# Controller.net
KiCad netlist of a schematic drawn in Altium Designer
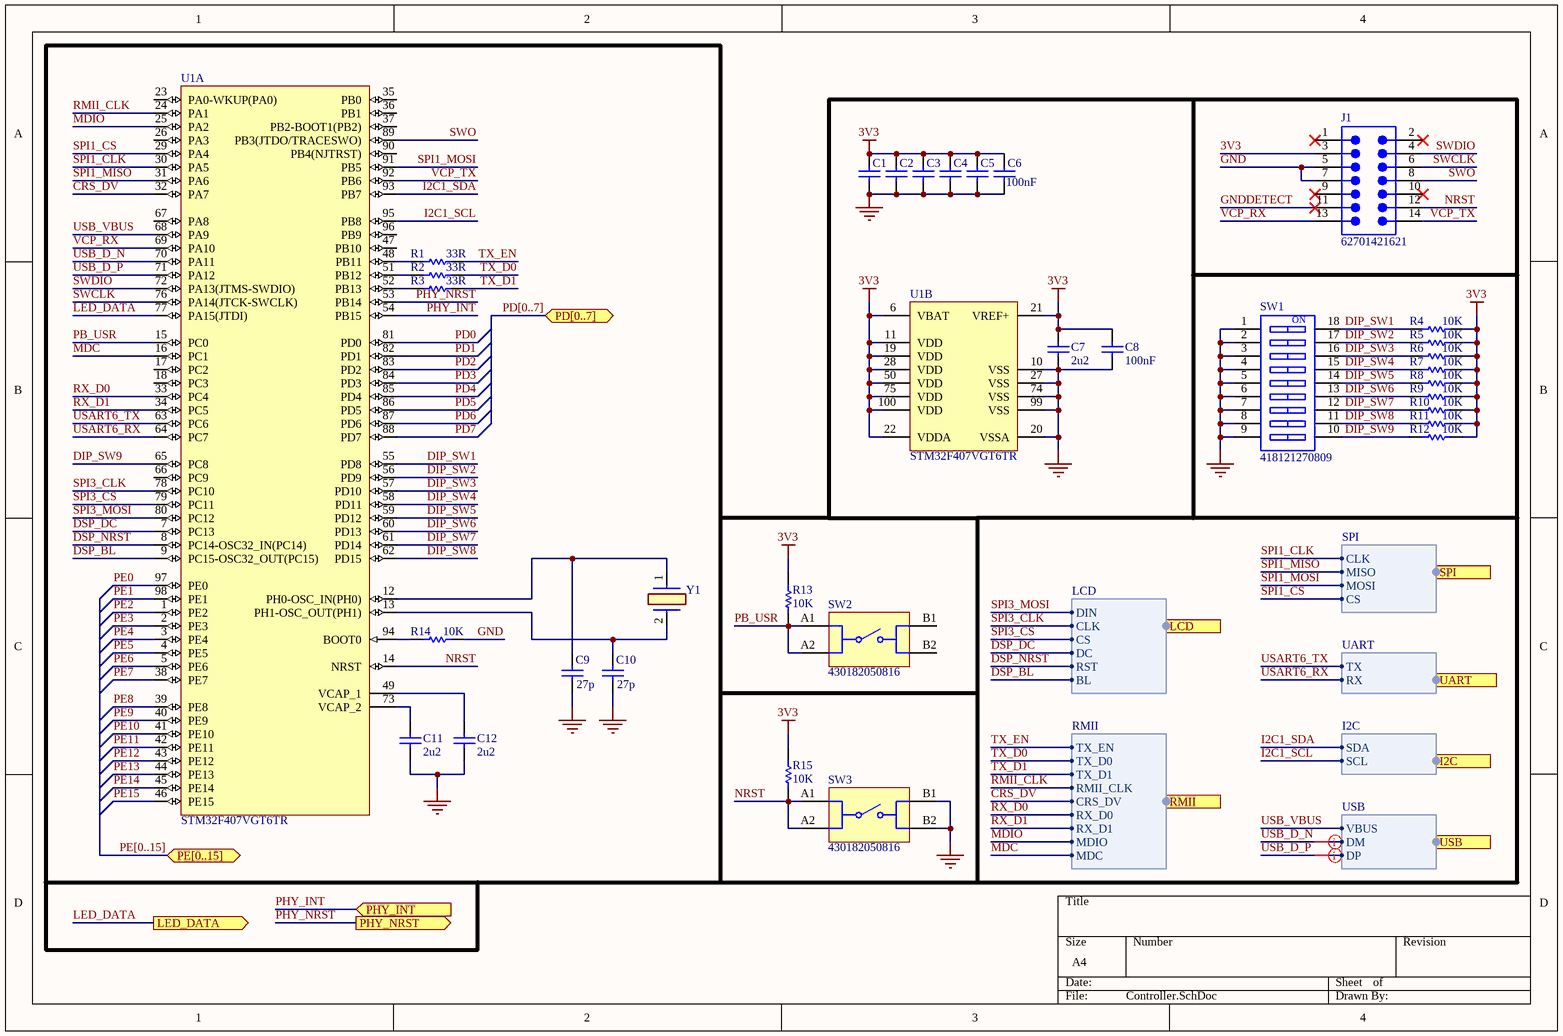
[diagram p0: Controller.SchDoc]

(export (version "E")
  (design (tool "Eeschema 10.0.6"))
  (components
    (comp (ref "C1")
      (value "100nF")
      (footprint "0603")
      (description "Capacitor 100V \r\n0603")
      (libsource (lib "Schlib1") (part "C0603C104K1RACAUTO"))
    )
    (comp (ref "C2")
      (value "100nF")
      (footprint "0603")
      (description "Capacitor 100V \r\n0603")
      (libsource (lib "Schlib1") (part "C0603C104K1RACAUTO"))
    )
    (comp (ref "C3")
      (value "100nF")
      (footprint "0603")
      (description "Capacitor 100V \r\n0603")
      (libsource (lib "Schlib1") (part "C0603C104K1RACAUTO"))
    )
    (comp (ref "C4")
      (value "100nF")
      (footprint "0603")
      (description "Capacitor 100V \r\n0603")
      (libsource (lib "Schlib1") (part "C0603C104K1RACAUTO"))
    )
    (comp (ref "C5")
      (value "100nF")
      (footprint "0603")
      (description "Capacitor 100V \r\n0603")
      (libsource (lib "Schlib1") (part "C0603C104K1RACAUTO"))
    )
    (comp (ref "C6")
      (value "100nF")
      (footprint "0603")
      (description "Capacitor 100V \r\n0603")
      (libsource (lib "Schlib1") (part "C0603C104K1RACAUTO"))
    )
    (comp (ref "C7")
      (value "2u2")
      (footprint "1206")
      (description "Capacitor 50V\r\n1206")
      (libsource (lib "Schlib1") (part "C1206C225K5RACAUTO7210"))
    )
    (comp (ref "C8")
      (value "100nF")
      (footprint "0603")
      (description "Capacitor 100V \r\n0603")
      (libsource (lib "Schlib1") (part "C0603C104K1RACAUTO"))
    )
    (comp (ref "C9")
      (value "27p")
      (footprint "0603")
      (description "Capacitor 100V \r\n0603")
      (libsource (lib "Schlib1") (part "C0603C270K1HACTU"))
    )
    (comp (ref "C10")
      (value "27p")
      (footprint "0603")
      (description "Capacitor 100V \r\n0603")
      (libsource (lib "Schlib1") (part "C0603C270K1HACTU"))
    )
    (comp (ref "C11")
      (value "2u2")
      (footprint "1206")
      (description "Capacitor 50V\r\n1206")
      (libsource (lib "Schlib1") (part "C1206C225K5RACAUTO7210"))
    )
    (comp (ref "C12")
      (value "2u2")
      (footprint "1206")
      (description "Capacitor 50V\r\n1206")
      (libsource (lib "Schlib1") (part "C1206C225K5RACAUTO7210"))
    )
    (comp (ref "J1")
      (value "62701421621")
      (footprint "62701421621")
      (description "62701421621 Conn, Header, 14Pos, 2Row, 1.27Mm Rohs Compliant: Yes")
      (libsource (lib "Altium Content Vault") (part "Header_Male_2R_14P"))
    )
    (comp (ref "R1")
      (value "33R")
      (footprint "0603")
      (description "Resistor 0.1W")
      (libsource (lib "Schlib1") (part "CRCW060333R0FKEA"))
    )
    (comp (ref "R2")
      (value "33R")
      (footprint "0603")
      (description "Resistor 0.1W")
      (libsource (lib "Schlib1") (part "CRCW060333R0FKEA"))
    )
    (comp (ref "R3")
      (value "33R")
      (footprint "0603")
      (description "Resistor 0.1W")
      (libsource (lib "Schlib1") (part "CRCW060333R0FKEA"))
    )
    (comp (ref "R4")
      (value "10K")
      (footprint "0603")
      (description "Resistor 0.1W")
      (libsource (lib "Schlib1") (part "CRCW060310K0FKEA"))
    )
    (comp (ref "R5")
      (value "10K")
      (footprint "0603")
      (description "Resistor 0.1W")
      (libsource (lib "Schlib1") (part "CRCW060310K0FKEA"))
    )
    (comp (ref "R6")
      (value "10K")
      (footprint "0603")
      (description "Resistor 0.1W")
      (libsource (lib "Schlib1") (part "CRCW060310K0FKEA"))
    )
    (comp (ref "R7")
      (value "10K")
      (footprint "0603")
      (description "Resistor 0.1W")
      (libsource (lib "Schlib1") (part "CRCW060310K0FKEA"))
    )
    (comp (ref "R8")
      (value "10K")
      (footprint "0603")
      (description "Resistor 0.1W")
      (libsource (lib "Schlib1") (part "CRCW060310K0FKEA"))
    )
    (comp (ref "R9")
      (value "10K")
      (footprint "0603")
      (description "Resistor 0.1W")
      (libsource (lib "Schlib1") (part "CRCW060310K0FKEA"))
    )
    (comp (ref "R10")
      (value "10K")
      (footprint "0603")
      (description "Resistor 0.1W")
      (libsource (lib "Schlib1") (part "CRCW060310K0FKEA"))
    )
    (comp (ref "R11")
      (value "10K")
      (footprint "0603")
      (description "Resistor 0.1W")
      (libsource (lib "Schlib1") (part "CRCW060310K0FKEA"))
    )
    (comp (ref "R12")
      (value "10K")
      (footprint "0603")
      (description "Resistor 0.1W")
      (libsource (lib "Schlib1") (part "CRCW060310K0FKEA"))
    )
    (comp (ref "R13")
      (value "10K")
      (footprint "0603")
      (description "Resistor 0.1W")
      (libsource (lib "Schlib1") (part "CRCW060310K0FKEA"))
    )
    (comp (ref "R14")
      (value "10K")
      (footprint "0603")
      (description "Resistor 0.1W")
      (libsource (lib "Schlib1") (part "CRCW060310K0FKEA"))
    )
    (comp (ref "R15")
      (value "10K")
      (footprint "0603")
      (description "Resistor 0.1W")
      (libsource (lib "Schlib1") (part "CRCW060310K0FKEA"))
    )
    (comp (ref "SW1")
      (value "418121270809")
      (footprint "418121270809")
      (libsource (lib "Altium Content Vault") (part "DIP-9"))
    )
    (comp (ref "SW2")
      (value "430182050816")
      (footprint "430182050816")
      (description "Switch Tactile N.O. SPST Round Button Gull Wing 0.05A 12VDC 1000000Cycles 1.57N SMD Reel")
      (libsource (lib "Altium Content Vault") (part "SPST-NO_4P"))
    )
    (comp (ref "SW3")
      (value "430182050816")
      (footprint "430182050816")
      (description "Switch Tactile N.O. SPST Round Button Gull Wing 0.05A 12VDC 1000000Cycles 1.57N SMD Reel")
      (libsource (lib "Altium Content Vault") (part "SPST-NO_4P"))
    )
    (comp (ref "U1")
      (value "STM32F407VGT6TR")
      (footprint "STM-LQFP100_V")
      (fields (field (name "MANUFACTURER") "STMicroelectronics"))
      (libsource (lib "Altium Content Vault") (part "MC-ARM-STM32F40X_41X-SQ100"))
    )
    (comp (ref "Y1")
      (value "ABLS7M-16.000MHZ-B-2-T")
      (footprint "ABLS7")
      (description "Crystal or Oscillator")
      (fields (field (name "MOUSER PART NUMBER") "815-ABLS7M-16-B-2-T"))
      (libsource (lib "Schlib1") (part "ABLS7M-16.000MHZ-B-2-T"))
    )
  )
  (nets
    (net (code "7") (name "/CRS_DV") (class "Default")
      (node (ref "U1") (pin "32") (pinfunction "PA7_32") (pintype "bidirectional"))
    )
    (net (code "8") (name "/DIP_SW1") (class "Default")
      (node (ref "R4") (pin "1") (pinfunction "1_1") (pintype "passive"))
      (node (ref "SW1") (pin "18") (pinfunction "18_18") (pintype "passive"))
      (node (ref "U1") (pin "55") (pinfunction "PD8_55") (pintype "bidirectional"))
    )
    (net (code "9") (name "/DIP_SW2") (class "Default")
      (node (ref "R5") (pin "1") (pinfunction "1_1") (pintype "passive"))
      (node (ref "SW1") (pin "17") (pinfunction "17_17") (pintype "passive"))
      (node (ref "U1") (pin "56") (pinfunction "PD9_56") (pintype "bidirectional"))
    )
    (net (code "10") (name "/DIP_SW3") (class "Default")
      (node (ref "R6") (pin "1") (pinfunction "1_1") (pintype "passive"))
      (node (ref "SW1") (pin "16") (pinfunction "16_16") (pintype "passive"))
      (node (ref "U1") (pin "57") (pinfunction "PD10_57") (pintype "bidirectional"))
    )
    (net (code "11") (name "/DIP_SW4") (class "Default")
      (node (ref "R7") (pin "1") (pinfunction "1_1") (pintype "passive"))
      (node (ref "SW1") (pin "15") (pinfunction "15_15") (pintype "passive"))
      (node (ref "U1") (pin "58") (pinfunction "PD11_58") (pintype "bidirectional"))
    )
    (net (code "12") (name "/DIP_SW5") (class "Default")
      (node (ref "R8") (pin "1") (pinfunction "1_1") (pintype "passive"))
      (node (ref "SW1") (pin "14") (pinfunction "14_14") (pintype "passive"))
      (node (ref "U1") (pin "59") (pinfunction "PD12_59") (pintype "bidirectional"))
    )
    (net (code "13") (name "/DIP_SW6") (class "Default")
      (node (ref "R9") (pin "1") (pinfunction "1_1") (pintype "passive"))
      (node (ref "SW1") (pin "13") (pinfunction "13_13") (pintype "passive"))
      (node (ref "U1") (pin "60") (pinfunction "PD13_60") (pintype "bidirectional"))
    )
    (net (code "14") (name "/DIP_SW7") (class "Default")
      (node (ref "R10") (pin "1") (pinfunction "1_1") (pintype "passive"))
      (node (ref "SW1") (pin "12") (pinfunction "12_12") (pintype "passive"))
      (node (ref "U1") (pin "61") (pinfunction "PD14_61") (pintype "bidirectional"))
    )
    (net (code "15") (name "/DIP_SW8") (class "Default")
      (node (ref "R11") (pin "1") (pinfunction "1_1") (pintype "passive"))
      (node (ref "SW1") (pin "11") (pinfunction "11_11") (pintype "passive"))
      (node (ref "U1") (pin "62") (pinfunction "PD15_62") (pintype "bidirectional"))
    )
    (net (code "16") (name "/DIP_SW9") (class "Default")
      (node (ref "R12") (pin "1") (pinfunction "1_1") (pintype "passive"))
      (node (ref "SW1") (pin "10") (pinfunction "10_10") (pintype "passive"))
      (node (ref "U1") (pin "65") (pinfunction "PC8_65") (pintype "bidirectional"))
    )
    (net (code "17") (name "/DSP_BL") (class "Default")
      (node (ref "U1") (pin "9") (pinfunction "PC15-OSC32_OUT(PC15)_9") (pintype "bidirectional"))
    )
    (net (code "18") (name "/DSP_DC") (class "Default")
      (node (ref "U1") (pin "7") (pinfunction "PC13_7") (pintype "bidirectional"))
    )
    (net (code "19") (name "/DSP_NRST") (class "Default")
      (node (ref "U1") (pin "8") (pinfunction "PC14-OSC32_IN(PC14)_8") (pintype "bidirectional"))
    )
    (net (code "20") (name "/GNDDETECT") (class "Default")
      (node (ref "J1") (pin "11") (pinfunction "11_11") (pintype "passive+no_connect"))
    )
    (net (code "21") (name "/I2C1_SCL") (class "Default")
      (node (ref "U1") (pin "95") (pinfunction "PB8_95") (pintype "bidirectional"))
    )
    (net (code "22") (name "/I2C1_SDA") (class "Default")
      (node (ref "U1") (pin "93") (pinfunction "PB7_93") (pintype "bidirectional"))
    )
    (net (code "23") (name "/LED_DATA") (class "Default")
      (node (ref "U1") (pin "77") (pinfunction "PA15(JTDI)_77") (pintype "bidirectional"))
    )
    (net (code "24") (name "/MDC") (class "Default")
      (node (ref "U1") (pin "16") (pinfunction "PC1_16") (pintype "bidirectional"))
    )
    (net (code "25") (name "/MDIO") (class "Default")
      (node (ref "U1") (pin "25") (pinfunction "PA2_25") (pintype "bidirectional"))
    )
    (net (code "26") (name "/NRST") (class "Default")
      (node (ref "J1") (pin "12") (pinfunction "12_12") (pintype "passive"))
      (node (ref "R15") (pin "1") (pinfunction "1_1") (pintype "passive"))
      (node (ref "SW3") (pin "A1") (pinfunction "A1_A1") (pintype "passive"))
      (node (ref "SW3") (pin "A2") (pinfunction "A2_A2") (pintype "passive"))
      (node (ref "U1") (pin "14") (pinfunction "NRST_14") (pintype "bidirectional"))
    )
    (net (code "27") (name "/PB_USR") (class "Default")
      (node (ref "R13") (pin "1") (pinfunction "1_1") (pintype "passive"))
      (node (ref "SW2") (pin "A1") (pinfunction "A1_A1") (pintype "passive"))
      (node (ref "SW2") (pin "A2") (pinfunction "A2_A2") (pintype "passive"))
      (node (ref "U1") (pin "15") (pinfunction "PC0_15") (pintype "bidirectional"))
    )
    (net (code "28") (name "/PD0") (class "Default")
      (node (ref "U1") (pin "81") (pinfunction "PD0_81") (pintype "bidirectional"))
    )
    (net (code "29") (name "/PD1") (class "Default")
      (node (ref "U1") (pin "82") (pinfunction "PD1_82") (pintype "bidirectional"))
    )
    (net (code "30") (name "/PD2") (class "Default")
      (node (ref "U1") (pin "83") (pinfunction "PD2_83") (pintype "bidirectional"))
    )
    (net (code "31") (name "/PD3") (class "Default")
      (node (ref "U1") (pin "84") (pinfunction "PD3_84") (pintype "bidirectional"))
    )
    (net (code "32") (name "/PD4") (class "Default")
      (node (ref "U1") (pin "85") (pinfunction "PD4_85") (pintype "bidirectional"))
    )
    (net (code "33") (name "/PD5") (class "Default")
      (node (ref "U1") (pin "86") (pinfunction "PD5_86") (pintype "bidirectional"))
    )
    (net (code "34") (name "/PD6") (class "Default")
      (node (ref "U1") (pin "87") (pinfunction "PD6_87") (pintype "bidirectional"))
    )
    (net (code "35") (name "/PD7") (class "Default")
      (node (ref "U1") (pin "88") (pinfunction "PD7_88") (pintype "bidirectional"))
    )
    (net (code "37") (name "/PE0") (class "Default")
      (node (ref "U1") (pin "97") (pinfunction "PE0_97") (pintype "bidirectional"))
    )
    (net (code "38") (name "/PE1") (class "Default")
      (node (ref "U1") (pin "98") (pinfunction "PE1_98") (pintype "bidirectional"))
    )
    (net (code "39") (name "/PE2") (class "Default")
      (node (ref "U1") (pin "1") (pinfunction "PE2_1") (pintype "bidirectional"))
    )
    (net (code "40") (name "/PE3") (class "Default")
      (node (ref "U1") (pin "2") (pinfunction "PE3_2") (pintype "bidirectional"))
    )
    (net (code "41") (name "/PE4") (class "Default")
      (node (ref "U1") (pin "3") (pinfunction "PE4_3") (pintype "bidirectional"))
    )
    (net (code "42") (name "/PE5") (class "Default")
      (node (ref "U1") (pin "4") (pinfunction "PE5_4") (pintype "bidirectional"))
    )
    (net (code "43") (name "/PE6") (class "Default")
      (node (ref "U1") (pin "5") (pinfunction "PE6_5") (pintype "bidirectional"))
    )
    (net (code "44") (name "/PE7") (class "Default")
      (node (ref "U1") (pin "38") (pinfunction "PE7_38") (pintype "bidirectional"))
    )
    (net (code "45") (name "/PE8") (class "Default")
      (node (ref "U1") (pin "39") (pinfunction "PE8_39") (pintype "bidirectional"))
    )
    (net (code "46") (name "/PE9") (class "Default")
      (node (ref "U1") (pin "40") (pinfunction "PE9_40") (pintype "bidirectional"))
    )
    (net (code "47") (name "/PE10") (class "Default")
      (node (ref "U1") (pin "41") (pinfunction "PE10_41") (pintype "bidirectional"))
    )
    (net (code "48") (name "/PE11") (class "Default")
      (node (ref "U1") (pin "42") (pinfunction "PE11_42") (pintype "bidirectional"))
    )
    (net (code "49") (name "/PE12") (class "Default")
      (node (ref "U1") (pin "43") (pinfunction "PE12_43") (pintype "bidirectional"))
    )
    (net (code "50") (name "/PE13") (class "Default")
      (node (ref "U1") (pin "44") (pinfunction "PE13_44") (pintype "bidirectional"))
    )
    (net (code "51") (name "/PE14") (class "Default")
      (node (ref "U1") (pin "45") (pinfunction "PE14_45") (pintype "bidirectional"))
    )
    (net (code "52") (name "/PE15") (class "Default")
      (node (ref "U1") (pin "46") (pinfunction "PE15_46") (pintype "bidirectional"))
    )
    (net (code "54") (name "/PHY_INT") (class "Default")
      (node (ref "U1") (pin "54") (pinfunction "PB15_54") (pintype "bidirectional"))
    )
    (net (code "55") (name "/PHY_NRST") (class "Default")
      (node (ref "U1") (pin "53") (pinfunction "PB14_53") (pintype "bidirectional"))
    )
    (net (code "56") (name "/RMII_CLK") (class "Default")
      (node (ref "U1") (pin "24") (pinfunction "PA1_24") (pintype "bidirectional"))
    )
    (net (code "57") (name "/RX_D0") (class "Default")
      (node (ref "U1") (pin "33") (pinfunction "PC4_33") (pintype "bidirectional"))
    )
    (net (code "58") (name "/RX_D1") (class "Default")
      (node (ref "U1") (pin "34") (pinfunction "PC5_34") (pintype "bidirectional"))
    )
    (net (code "59") (name "/SPI1_CLK") (class "Default")
      (node (ref "U1") (pin "30") (pinfunction "PA5_30") (pintype "bidirectional"))
    )
    (net (code "60") (name "/SPI1_CS") (class "Default")
      (node (ref "U1") (pin "29") (pinfunction "PA4_29") (pintype "bidirectional"))
    )
    (net (code "61") (name "/SPI1_MISO") (class "Default")
      (node (ref "U1") (pin "31") (pinfunction "PA6_31") (pintype "bidirectional"))
    )
    (net (code "62") (name "/SPI1_MOSI") (class "Default")
      (node (ref "U1") (pin "91") (pinfunction "PB5_91") (pintype "bidirectional"))
    )
    (net (code "63") (name "/SPI3_CLK") (class "Default")
      (node (ref "U1") (pin "78") (pinfunction "PC10_78") (pintype "bidirectional"))
    )
    (net (code "64") (name "/SPI3_CS") (class "Default")
      (node (ref "U1") (pin "79") (pinfunction "PC11_79") (pintype "bidirectional"))
    )
    (net (code "65") (name "/SPI3_MOSI") (class "Default")
      (node (ref "U1") (pin "80") (pinfunction "PC12_80") (pintype "bidirectional"))
    )
    (net (code "66") (name "/SWCLK") (class "Default")
      (node (ref "J1") (pin "6") (pinfunction "6_6") (pintype "passive"))
      (node (ref "U1") (pin "76") (pinfunction "PA14(JTCK-SWCLK)_76") (pintype "bidirectional"))
    )
    (net (code "67") (name "/SWDIO") (class "Default")
      (node (ref "J1") (pin "4") (pinfunction "4_4") (pintype "passive"))
      (node (ref "U1") (pin "72") (pinfunction "PA13(JTMS-SWDIO)_72") (pintype "bidirectional"))
    )
    (net (code "68") (name "/SWO") (class "Default")
      (node (ref "J1") (pin "8") (pinfunction "8_8") (pintype "passive"))
      (node (ref "U1") (pin "89") (pinfunction "PB3(JTDO/TRACESWO)_89") (pintype "bidirectional"))
    )
    (net (code "69") (name "/TX_D0") (class "Default")
      (node (ref "R2") (pin "2") (pinfunction "2_2") (pintype "passive"))
    )
    (net (code "70") (name "/TX_D1") (class "Default")
      (node (ref "R3") (pin "2") (pinfunction "2_2") (pintype "passive"))
    )
    (net (code "71") (name "/TX_EN") (class "Default")
      (node (ref "R1") (pin "2") (pinfunction "2_2") (pintype "passive"))
    )
    (net (code "72") (name "/USART6_RX") (class "Default")
      (node (ref "U1") (pin "64") (pinfunction "PC7_64") (pintype "bidirectional"))
    )
    (net (code "73") (name "/USART6_TX") (class "Default")
      (node (ref "U1") (pin "63") (pinfunction "PC6_63") (pintype "bidirectional"))
    )
    (net (code "74") (name "/USB_D_N") (class "Default")
      (node (ref "U1") (pin "70") (pinfunction "PA11_70") (pintype "bidirectional"))
    )
    (net (code "75") (name "/USB_D_P") (class "Default")
      (node (ref "U1") (pin "71") (pinfunction "PA12_71") (pintype "bidirectional"))
    )
    (net (code "76") (name "/USB_VBUS") (class "Default")
      (node (ref "U1") (pin "68") (pinfunction "PA9_68") (pintype "bidirectional"))
    )
    (net (code "77") (name "/VCP_RX") (class "Default")
      (node (ref "J1") (pin "13") (pinfunction "13_13") (pintype "passive"))
      (node (ref "U1") (pin "69") (pinfunction "PA10_69") (pintype "bidirectional"))
    )
    (net (code "78") (name "/VCP_TX") (class "Default")
      (node (ref "J1") (pin "14") (pinfunction "14_14") (pintype "passive"))
      (node (ref "U1") (pin "92") (pinfunction "PB6_92") (pintype "bidirectional"))
    )
    (net (code "85") (name "3V3") (class "Default")
      (node (ref "C1") (pin "2") (pinfunction "2_2") (pintype "passive"))
      (node (ref "C2") (pin "2") (pinfunction "2_2") (pintype "passive"))
      (node (ref "C3") (pin "2") (pinfunction "2_2") (pintype "passive"))
      (node (ref "C4") (pin "2") (pinfunction "2_2") (pintype "passive"))
      (node (ref "C5") (pin "2") (pinfunction "2_2") (pintype "passive"))
      (node (ref "C6") (pin "2") (pinfunction "2_2") (pintype "passive"))
      (node (ref "C7") (pin "2") (pinfunction "2_2") (pintype "passive"))
      (node (ref "C8") (pin "2") (pinfunction "2_2") (pintype "passive"))
      (node (ref "J1") (pin "3") (pinfunction "3_3") (pintype "passive"))
      (node (ref "R10") (pin "2") (pinfunction "2_2") (pintype "passive"))
      (node (ref "R11") (pin "2") (pinfunction "2_2") (pintype "passive"))
      (node (ref "R12") (pin "2") (pinfunction "2_2") (pintype "passive"))
      (node (ref "R13") (pin "2") (pinfunction "2_2") (pintype "passive"))
      (node (ref "R15") (pin "2") (pinfunction "2_2") (pintype "passive"))
      (node (ref "R4") (pin "2") (pinfunction "2_2") (pintype "passive"))
      (node (ref "R5") (pin "2") (pinfunction "2_2") (pintype "passive"))
      (node (ref "R6") (pin "2") (pinfunction "2_2") (pintype "passive"))
      (node (ref "R7") (pin "2") (pinfunction "2_2") (pintype "passive"))
      (node (ref "R8") (pin "2") (pinfunction "2_2") (pintype "passive"))
      (node (ref "R9") (pin "2") (pinfunction "2_2") (pintype "passive"))
      (node (ref "U1") (pin "100") (pinfunction "VDD_100") (pintype "power_in"))
      (node (ref "U1") (pin "11") (pinfunction "VDD_11") (pintype "power_in"))
      (node (ref "U1") (pin "19") (pinfunction "VDD_19") (pintype "power_in"))
      (node (ref "U1") (pin "21") (pinfunction "VREF+_21") (pintype "power_in"))
      (node (ref "U1") (pin "22") (pinfunction "VDDA_22") (pintype "power_in"))
      (node (ref "U1") (pin "28") (pinfunction "VDD_28") (pintype "power_in"))
      (node (ref "U1") (pin "50") (pinfunction "VDD_50") (pintype "power_in"))
      (node (ref "U1") (pin "6") (pinfunction "VBAT_6") (pintype "power_in"))
      (node (ref "U1") (pin "75") (pinfunction "VDD_75") (pintype "power_in"))
    )
    (net (code "86") (name "GND") (class "Default")
      (node (ref "C1") (pin "1") (pinfunction "1_1") (pintype "passive"))
      (node (ref "C10") (pin "1") (pinfunction "1_1") (pintype "passive"))
      (node (ref "C11") (pin "1") (pinfunction "1_1") (pintype "passive"))
      (node (ref "C12") (pin "1") (pinfunction "1_1") (pintype "passive"))
      (node (ref "C2") (pin "1") (pinfunction "1_1") (pintype "passive"))
      (node (ref "C3") (pin "1") (pinfunction "1_1") (pintype "passive"))
      (node (ref "C4") (pin "1") (pinfunction "1_1") (pintype "passive"))
      (node (ref "C5") (pin "1") (pinfunction "1_1") (pintype "passive"))
      (node (ref "C6") (pin "1") (pinfunction "1_1") (pintype "passive"))
      (node (ref "C7") (pin "1") (pinfunction "1_1") (pintype "passive"))
      (node (ref "C8") (pin "1") (pinfunction "1_1") (pintype "passive"))
      (node (ref "C9") (pin "1") (pinfunction "1_1") (pintype "passive"))
      (node (ref "J1") (pin "5") (pinfunction "5_5") (pintype "passive"))
      (node (ref "J1") (pin "7") (pinfunction "7_7") (pintype "passive"))
      (node (ref "R14") (pin "2") (pinfunction "2_2") (pintype "passive"))
      (node (ref "SW1") (pin "1") (pinfunction "1_1") (pintype "passive"))
      (node (ref "SW1") (pin "2") (pinfunction "2_2") (pintype "passive"))
      (node (ref "SW1") (pin "3") (pinfunction "3_3") (pintype "passive"))
      (node (ref "SW1") (pin "4") (pinfunction "4_4") (pintype "passive"))
      (node (ref "SW1") (pin "5") (pinfunction "5_5") (pintype "passive"))
      (node (ref "SW1") (pin "6") (pinfunction "6_6") (pintype "passive"))
      (node (ref "SW1") (pin "7") (pinfunction "7_7") (pintype "passive"))
      (node (ref "SW1") (pin "8") (pinfunction "8_8") (pintype "passive"))
      (node (ref "SW1") (pin "9") (pinfunction "9_9") (pintype "passive"))
      (node (ref "SW3") (pin "B1") (pinfunction "B1_B1") (pintype "passive"))
      (node (ref "SW3") (pin "B2") (pinfunction "B2_B2") (pintype "passive"))
      (node (ref "U1") (pin "10") (pinfunction "VSS_10") (pintype "power_in"))
      (node (ref "U1") (pin "20") (pinfunction "VSSA_20") (pintype "power_in"))
      (node (ref "U1") (pin "27") (pinfunction "VSS_27") (pintype "power_in"))
      (node (ref "U1") (pin "74") (pinfunction "VSS_74") (pintype "power_in"))
      (node (ref "U1") (pin "99") (pinfunction "VSS_99") (pintype "power_in"))
    )
    (net (code "87") (name "Net-(U1A-BOOT0)") (class "Default")
      (node (ref "R14") (pin "1") (pinfunction "1_1") (pintype "passive"))
      (node (ref "U1") (pin "94") (pinfunction "BOOT0_94") (pintype "input"))
    )
    (net (code "88") (name "Net-(U1A-PB11)") (class "Default")
      (node (ref "R1") (pin "1") (pinfunction "1_1") (pintype "passive"))
      (node (ref "U1") (pin "48") (pinfunction "PB11_48") (pintype "bidirectional"))
    )
    (net (code "89") (name "Net-(U1A-PB12)") (class "Default")
      (node (ref "R2") (pin "1") (pinfunction "1_1") (pintype "passive"))
      (node (ref "U1") (pin "51") (pinfunction "PB12_51") (pintype "bidirectional"))
    )
    (net (code "90") (name "Net-(U1A-PB13)") (class "Default")
      (node (ref "R3") (pin "1") (pinfunction "1_1") (pintype "passive"))
      (node (ref "U1") (pin "52") (pinfunction "PB13_52") (pintype "bidirectional"))
    )
    (net (code "91") (name "Net-(U1A-PH0-OSC_IN(PH0))") (class "Default")
      (node (ref "C9") (pin "2") (pinfunction "2_2") (pintype "passive"))
      (node (ref "U1") (pin "12") (pinfunction "PH0-OSC_IN(PH0)_12") (pintype "bidirectional"))
      (node (ref "Y1") (pin "1") (pinfunction "1_1") (pintype "passive"))
    )
    (net (code "92") (name "Net-(U1A-PH1-OSC_OUT(PH1))") (class "Default")
      (node (ref "C10") (pin "2") (pinfunction "2_2") (pintype "passive"))
      (node (ref "U1") (pin "13") (pinfunction "PH1-OSC_OUT(PH1)_13") (pintype "bidirectional"))
      (node (ref "Y1") (pin "2") (pinfunction "2_2") (pintype "passive"))
    )
    (net (code "93") (name "Net-(U1A-VCAP_1)") (class "Default")
      (node (ref "C12") (pin "2") (pinfunction "2_2") (pintype "passive"))
      (node (ref "U1") (pin "49") (pinfunction "VCAP_1_49") (pintype "power_in"))
    )
    (net (code "94") (name "Net-(U1A-VCAP_2)") (class "Default")
      (node (ref "C11") (pin "2") (pinfunction "2_2") (pintype "passive"))
      (node (ref "U1") (pin "73") (pinfunction "VCAP_2_73") (pintype "power_in"))
    )
    (net (code "95") (name "unconnected-(J1-Pad1)") (class "Default")
      (node (ref "J1") (pin "1") (pinfunction "1_1") (pintype "passive+no_connect"))
    )
    (net (code "96") (name "unconnected-(J1-Pad2)") (class "Default")
      (node (ref "J1") (pin "2") (pinfunction "2_2") (pintype "passive+no_connect"))
    )
    (net (code "97") (name "unconnected-(J1-Pad9)") (class "Default")
      (node (ref "J1") (pin "9") (pinfunction "9_9") (pintype "passive+no_connect"))
    )
    (net (code "98") (name "unconnected-(J1-Pad10)") (class "Default")
      (node (ref "J1") (pin "10") (pinfunction "10_10") (pintype "passive+no_connect"))
    )
    (net (code "99") (name "unconnected-(SW2-PadB1)") (class "Default")
      (node (ref "SW2") (pin "B1") (pinfunction "B1_B1") (pintype "passive"))
    )
    (net (code "100") (name "unconnected-(SW2-PadB2)") (class "Default")
      (node (ref "SW2") (pin "B2") (pinfunction "B2_B2") (pintype "passive"))
    )
    (net (code "101") (name "unconnected-(U1A-PA0-WKUP(PA0)-Pad23)") (class "Default")
      (node (ref "U1") (pin "23") (pinfunction "PA0-WKUP(PA0)_23") (pintype "bidirectional"))
    )
    (net (code "102") (name "unconnected-(U1A-PA3-Pad26)") (class "Default")
      (node (ref "U1") (pin "26") (pinfunction "PA3_26") (pintype "bidirectional"))
    )
    (net (code "103") (name "unconnected-(U1A-PA8-Pad67)") (class "Default")
      (node (ref "U1") (pin "67") (pinfunction "PA8_67") (pintype "bidirectional"))
    )
    (net (code "104") (name "unconnected-(U1A-PB0-Pad35)") (class "Default")
      (node (ref "U1") (pin "35") (pinfunction "PB0_35") (pintype "bidirectional"))
    )
    (net (code "105") (name "unconnected-(U1A-PB1-Pad36)") (class "Default")
      (node (ref "U1") (pin "36") (pinfunction "PB1_36") (pintype "bidirectional"))
    )
    (net (code "106") (name "unconnected-(U1A-PB2-BOOT1(PB2)-Pad37)") (class "Default")
      (node (ref "U1") (pin "37") (pinfunction "PB2-BOOT1(PB2)_37") (pintype "bidirectional"))
    )
    (net (code "107") (name "unconnected-(U1A-PB4(NJTRST)-Pad90)") (class "Default")
      (node (ref "U1") (pin "90") (pinfunction "PB4(NJTRST)_90") (pintype "bidirectional"))
    )
    (net (code "108") (name "unconnected-(U1A-PB9-Pad96)") (class "Default")
      (node (ref "U1") (pin "96") (pinfunction "PB9_96") (pintype "bidirectional"))
    )
    (net (code "109") (name "unconnected-(U1A-PB10-Pad47)") (class "Default")
      (node (ref "U1") (pin "47") (pinfunction "PB10_47") (pintype "bidirectional"))
    )
    (net (code "110") (name "unconnected-(U1A-PC2-Pad17)") (class "Default")
      (node (ref "U1") (pin "17") (pinfunction "PC2_17") (pintype "bidirectional"))
    )
    (net (code "111") (name "unconnected-(U1A-PC3-Pad18)") (class "Default")
      (node (ref "U1") (pin "18") (pinfunction "PC3_18") (pintype "bidirectional"))
    )
    (net (code "112") (name "unconnected-(U1A-PC9-Pad66)") (class "Default")
      (node (ref "U1") (pin "66") (pinfunction "PC9_66") (pintype "bidirectional"))
    )
  )
)
